# RX_Pre.net
KiCad netlist of a schematic drawn in Altium Designer
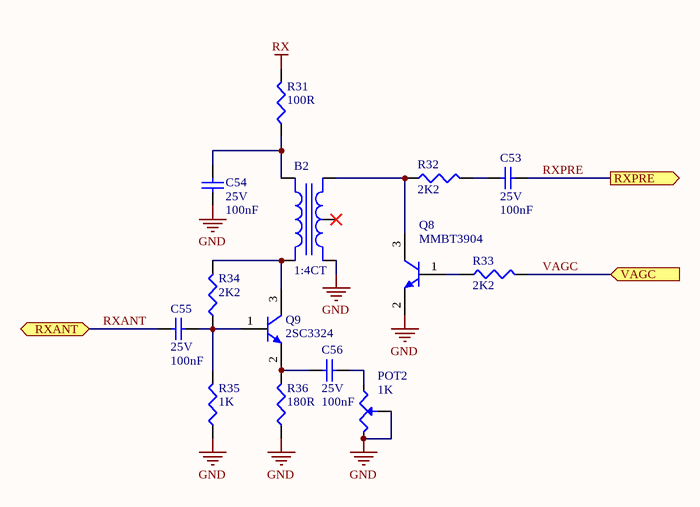
[diagram p0: RX_Pre.SchDoc]

(export (version "E")
  (design (tool "Eeschema 10.0.6"))
  (components
    (comp (ref "B2")
      (value "1:4CT")
      (footprint "CX2047LANL")
      (description "Balun 4CT:1")
      (libsource (lib "NavarroIND") (part "BALUN CX2047LANL"))
    )
    (comp (ref "C53")
      (value "100nF")
      (footprint "CC0603")
      (description "Capacitor (Semiconductor SIM Model)")
      (fields (field (name "TENSÃO") "25V") (field (name "Comment") "Capacitor Cerâmico"))
      (libsource (lib "NavarroCAP") (part "Cap 100nF 25V 0603 X7R"))
    )
    (comp (ref "C54")
      (value "100nF")
      (footprint "CC0603")
      (description "Capacitor (Semiconductor SIM Model)")
      (fields (field (name "TENSÃO") "25V") (field (name "Comment") "Capacitor Cerâmico"))
      (libsource (lib "NavarroCAP") (part "Cap 100nF 25V 0603 X7R"))
    )
    (comp (ref "C55")
      (value "100nF")
      (footprint "CC0603")
      (description "Capacitor (Semiconductor SIM Model)")
      (fields (field (name "TENSÃO") "25V") (field (name "Comment") "Capacitor Cerâmico"))
      (libsource (lib "NavarroCAP") (part "Cap 100nF 25V 0603 X7R"))
    )
    (comp (ref "C56")
      (value "100nF")
      (footprint "CC0603")
      (description "Capacitor (Semiconductor SIM Model)")
      (fields (field (name "TENSÃO") "25V") (field (name "Comment") "Capacitor Cerâmico"))
      (libsource (lib "NavarroCAP") (part "Cap 100nF 25V 0603 X7R"))
    )
    (comp (ref "POT2")
      (value "1K")
      (footprint "POT - PTV09")
      (description "Potenciometro")
      (fields (field (name "Comment") "Potenciômetro"))
      (libsource (lib "NavarroRES") (part "POT 100k Audio"))
    )
    (comp (ref "Q8")
      (value "MMBT3904")
      (footprint "SOT-23-3N")
      (description "NPN General Purpose Amplifier")
      (libsource (lib "NavarroSEMI") (part "TRS MMBT3904 40V 200mA SOT-23-3N"))
    )
    (comp (ref "Q9")
      (value "2SC3324")
      (footprint "SOT-23-3N")
      (description "NPN General Purpose Amplifier")
      (libsource (lib "NavarroSEMI") (part "TRS 2SC3324 120V 100mA SOT-23-3"))
    )
    (comp (ref "R31")
      (value "100R")
      (footprint "CC0603")
      (description "Resistor")
      (libsource (lib "NavarroRES") (part "Res 100R 5% 0603 1/10W"))
    )
    (comp (ref "R32")
      (value "2K2")
      (footprint "CC0603")
      (description "Resistor")
      (libsource (lib "NavarroRES") (part "Res 2K2 5% 0603 1/10W"))
    )
    (comp (ref "R33")
      (value "2K2")
      (footprint "CC0603")
      (description "Resistor")
      (libsource (lib "NavarroRES") (part "Res 2K2 5% 0603 1/10W"))
    )
    (comp (ref "R34")
      (value "2K2")
      (footprint "CC0603")
      (description "Resistor")
      (libsource (lib "NavarroRES") (part "Res 2K2 5% 0603 1/10W"))
    )
    (comp (ref "R35")
      (value "1K")
      (footprint "CC0603")
      (description "Resistor")
      (libsource (lib "NavarroRES") (part "Res 1K 1% 0603 1/10W"))
    )
    (comp (ref "R36")
      (value "180R")
      (footprint "CC0603")
      (description "Resistor")
      (libsource (lib "NavarroRES") (part "Res 180R 1% 0603 1/10W"))
    )
  )
  (nets
    (net (code "1") (name "/RXANT") (class "Default")
      (node (ref "C55") (pin "2") (pinfunction "2_2") (pintype "passive"))
    )
    (net (code "2") (name "/RXPRE") (class "Default")
      (node (ref "C53") (pin "1") (pinfunction "1_1") (pintype "passive"))
    )
    (net (code "3") (name "/VAGC") (class "Default")
      (node (ref "R33") (pin "2") (pinfunction "2_2") (pintype "passive"))
    )
    (net (code "4") (name "GND") (class "Default")
      (node (ref "B2") (pin "3") (pinfunction "Pri-_3") (pintype "passive"))
      (node (ref "C54") (pin "1") (pinfunction "1_1") (pintype "passive"))
      (node (ref "POT2") (pin "2") (pinfunction "TAP_2") (pintype "passive"))
      (node (ref "POT2") (pin "3") (pinfunction "3_3") (pintype "passive"))
      (node (ref "Q8") (pin "2") (pinfunction "E_2") (pintype "passive"))
      (node (ref "R35") (pin "1") (pinfunction "1_1") (pintype "passive"))
      (node (ref "R36") (pin "1") (pinfunction "1_1") (pintype "passive"))
    )
    (net (code "5") (name "Net-(B2-Pri+)") (class "Default")
      (node (ref "B2") (pin "4") (pinfunction "Pri+_4") (pintype "passive"))
      (node (ref "Q9") (pin "3") (pinfunction "C_3") (pintype "passive"))
      (node (ref "R34") (pin "2") (pinfunction "2_2") (pintype "passive"))
    )
    (net (code "6") (name "Net-(B2-Sec-)") (class "Default")
      (node (ref "B2") (pin "6") (pinfunction "Sec-_6") (pintype "passive"))
      (node (ref "C54") (pin "2") (pinfunction "2_2") (pintype "passive"))
      (node (ref "R31") (pin "1") (pinfunction "1_1") (pintype "passive"))
    )
    (net (code "7") (name "Net-(C53-Pad2)") (class "Default")
      (node (ref "C53") (pin "2") (pinfunction "2_2") (pintype "passive"))
      (node (ref "R32") (pin "2") (pinfunction "2_2") (pintype "passive"))
    )
    (net (code "8") (name "Net-(C56-Pad1)") (class "Default")
      (node (ref "C56") (pin "1") (pinfunction "1_1") (pintype "passive"))
      (node (ref "POT2") (pin "1") (pinfunction "1_1") (pintype "passive"))
    )
    (net (code "9") (name "Net-(Q8-B)") (class "Default")
      (node (ref "Q8") (pin "1") (pinfunction "B_1") (pintype "passive"))
      (node (ref "R33") (pin "1") (pinfunction "1_1") (pintype "passive"))
    )
    (net (code "10") (name "Net-(Q8-C)") (class "Default")
      (node (ref "B2") (pin "1") (pinfunction "Sec+_1") (pintype "passive"))
      (node (ref "Q8") (pin "3") (pinfunction "C_3") (pintype "passive"))
      (node (ref "R32") (pin "1") (pinfunction "1_1") (pintype "passive"))
    )
    (net (code "11") (name "Net-(Q9-B)") (class "Default")
      (node (ref "C55") (pin "1") (pinfunction "1_1") (pintype "passive"))
      (node (ref "Q9") (pin "1") (pinfunction "B_1") (pintype "passive"))
      (node (ref "R34") (pin "1") (pinfunction "1_1") (pintype "passive"))
      (node (ref "R35") (pin "2") (pinfunction "2_2") (pintype "passive"))
    )
    (net (code "12") (name "Net-(Q9-E)") (class "Default")
      (node (ref "C56") (pin "2") (pinfunction "2_2") (pintype "passive"))
      (node (ref "Q9") (pin "2") (pinfunction "E_2") (pintype "passive"))
      (node (ref "R36") (pin "2") (pinfunction "2_2") (pintype "passive"))
    )
    (net (code "13") (name "RX") (class "Default")
      (node (ref "R31") (pin "2") (pinfunction "2_2") (pintype "passive"))
    )
    (net (code "14") (name "unconnected-(B2-Sec+-Pad2)") (class "Default")
      (node (ref "B2") (pin "2") (pinfunction "Sec+_2") (pintype "passive+no_connect"))
    )
  )
)
